# Keys.net
KiCad netlist of a schematic drawn in Altium Designer
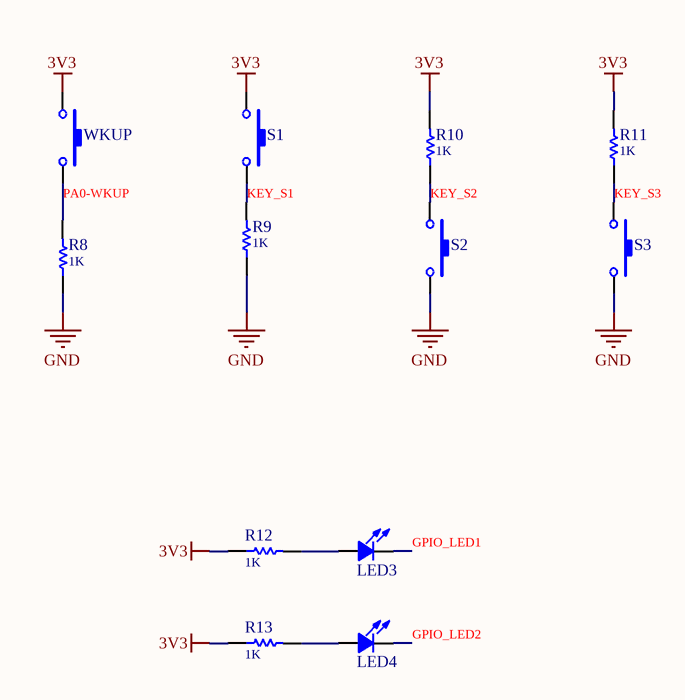
[diagram p0: Keys.SchDoc]

(export (version "E")
  (design (tool "Eeschema 10.0.6"))
  (components
    (comp (ref "LED3")
      (value "LED")
      (footprint "Led-0805_L")
      (description "发光二极管")
      (libsource (lib "XuZhe") (part "LED"))
    )
    (comp (ref "LED4")
      (value "LED")
      (footprint "Led-0805_L")
      (description "发光二极管")
      (libsource (lib "XuZhe") (part "LED"))
    )
    (comp (ref "R8")
      (value "1K")
      (footprint "R0603-L")
      (description "贴片电阻")
      (fields (field (name "Comment") "R"))
      (libsource (lib "XuZhe") (part "Res"))
    )
    (comp (ref "R9")
      (value "1K")
      (footprint "R0603-L")
      (description "贴片电阻")
      (fields (field (name "Comment") "R"))
      (libsource (lib "XuZhe") (part "Res"))
    )
    (comp (ref "R10")
      (value "1K")
      (footprint "R0603-L")
      (description "贴片电阻")
      (fields (field (name "Comment") "R"))
      (libsource (lib "XuZhe") (part "Res"))
    )
    (comp (ref "R11")
      (value "1K")
      (footprint "R0603-L")
      (description "贴片电阻")
      (fields (field (name "Comment") "R"))
      (libsource (lib "XuZhe") (part "Res"))
    )
    (comp (ref "R12")
      (value "1K")
      (footprint "R0603-L")
      (description "贴片电阻")
      (fields (field (name "Comment") "R"))
      (libsource (lib "XuZhe") (part "Res"))
    )
    (comp (ref "R13")
      (value "1K")
      (footprint "R0603-L")
      (description "贴片电阻")
      (fields (field (name "Comment") "R"))
      (libsource (lib "XuZhe") (part "Res"))
    )
    (comp (ref "S1")
      (value "SW-PB2")
      (footprint "SW-PB2-SMD")
      (description "贴片式2脚微动开关")
      (libsource (lib "XuZhe") (part "SW-PB2"))
    )
    (comp (ref "S2")
      (value "SW-PB2")
      (footprint "SW-PB2-SMD")
      (description "贴片式2脚微动开关")
      (libsource (lib "XuZhe") (part "SW-PB2"))
    )
    (comp (ref "S3")
      (value "SW-PB2")
      (footprint "SW-PB2-SMD")
      (description "贴片式2脚微动开关")
      (libsource (lib "XuZhe") (part "SW-PB2"))
    )
    (comp (ref "WKUP")
      (value "SW-PB2")
      (footprint "SW-PB2-SMD")
      (description "贴片式2脚微动开关")
      (libsource (lib "XuZhe") (part "SW-PB2"))
    )
  )
  (nets
    (net (code "1") (name "/GPIO_LED1") (class "Default")
      (node (ref "LED3") (pin "2") (pinfunction "2_2") (pintype "passive"))
    )
    (net (code "2") (name "/GPIO_LED2") (class "Default")
      (node (ref "LED4") (pin "2") (pinfunction "2_2") (pintype "passive"))
    )
    (net (code "3") (name "/KEY_S1") (class "Default")
      (node (ref "R9") (pin "2") (pinfunction "2_2") (pintype "passive"))
      (node (ref "S1") (pin "2") (pinfunction "2_2") (pintype "passive"))
    )
    (net (code "4") (name "/KEY_S2") (class "Default")
      (node (ref "R10") (pin "1") (pinfunction "1_1") (pintype "passive"))
      (node (ref "S2") (pin "1") (pinfunction "1_1") (pintype "passive"))
    )
    (net (code "5") (name "/KEY_S3") (class "Default")
      (node (ref "R11") (pin "1") (pinfunction "1_1") (pintype "passive"))
      (node (ref "S3") (pin "1") (pinfunction "1_1") (pintype "passive"))
    )
    (net (code "6") (name "/PA0-WKUP") (class "Default")
      (node (ref "R8") (pin "2") (pinfunction "2_2") (pintype "passive"))
      (node (ref "WKUP") (pin "2") (pinfunction "2_2") (pintype "passive"))
    )
    (net (code "7") (name "3V3") (class "Default")
      (node (ref "R10") (pin "2") (pinfunction "2_2") (pintype "passive"))
      (node (ref "R11") (pin "2") (pinfunction "2_2") (pintype "passive"))
      (node (ref "R12") (pin "1") (pinfunction "1_1") (pintype "passive"))
      (node (ref "R13") (pin "1") (pinfunction "1_1") (pintype "passive"))
      (node (ref "S1") (pin "1") (pinfunction "1_1") (pintype "passive"))
      (node (ref "WKUP") (pin "1") (pinfunction "1_1") (pintype "passive"))
    )
    (net (code "8") (name "GND") (class "Default")
      (node (ref "R8") (pin "1") (pinfunction "1_1") (pintype "passive"))
      (node (ref "R9") (pin "1") (pinfunction "1_1") (pintype "passive"))
      (node (ref "S2") (pin "2") (pinfunction "2_2") (pintype "passive"))
      (node (ref "S3") (pin "2") (pinfunction "2_2") (pintype "passive"))
    )
    (net (code "9") (name "Net-(LED3-Pad1)") (class "Default")
      (node (ref "LED3") (pin "1") (pinfunction "1_1") (pintype "passive"))
      (node (ref "R12") (pin "2") (pinfunction "2_2") (pintype "passive"))
    )
    (net (code "10") (name "Net-(LED4-Pad1)") (class "Default")
      (node (ref "LED4") (pin "1") (pinfunction "1_1") (pintype "passive"))
      (node (ref "R13") (pin "2") (pinfunction "2_2") (pintype "passive"))
    )
  )
)
